# keypad.net
KiCad netlist of a schematic drawn in EAGLE
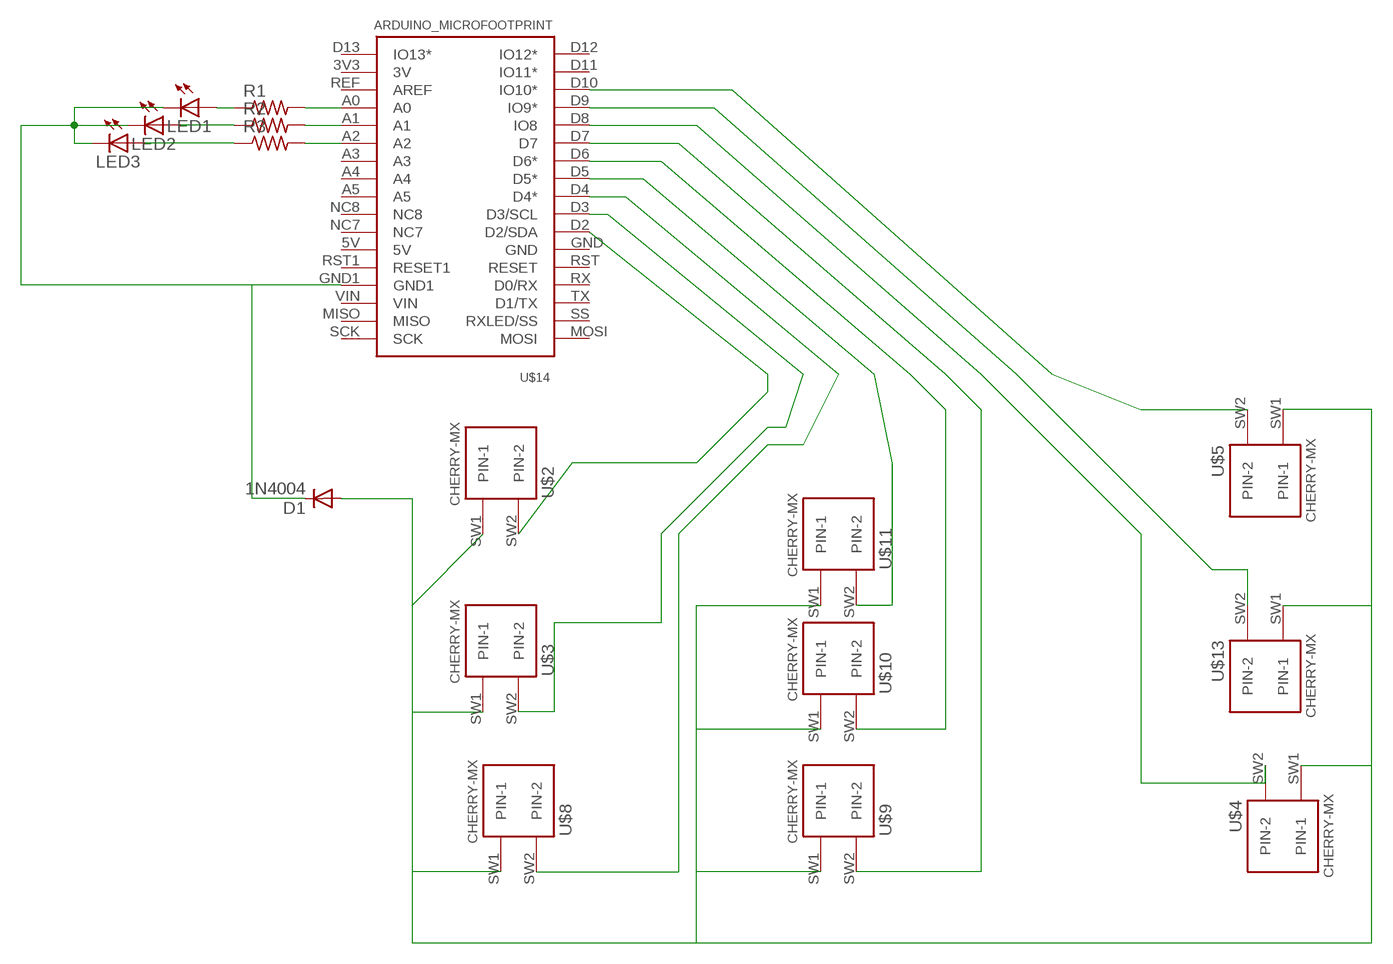
[diagram p0: schematic, sheet 1]

(export (version "E")
  (design (tool "Eeschema 10.0.6"))
  (components
    (comp (ref "D1")
      (value "1N4004")
      (footprint "eagle-import:DO41-10")
      (libsource (lib "eagle-import") (part "1N4004"))
    )
    (comp (ref "LED1")
      (value "LED5MM")
      (footprint "eagle-import:LED5MM")
      (libsource (lib "eagle-import") (part "LED5MM"))
    )
    (comp (ref "LED2")
      (value "LED5MM")
      (footprint "eagle-import:LED5MM")
      (libsource (lib "eagle-import") (part "LED5MM"))
    )
    (comp (ref "LED3")
      (value "LED5MM")
      (footprint "eagle-import:LED5MM")
      (libsource (lib "eagle-import") (part "LED5MM"))
    )
    (comp (ref "R1")
      (value "R-US_0207/5V")
      (footprint "eagle-import:0207_5V")
      (libsource (lib "eagle-import") (part "R-US_0207/5V"))
    )
    (comp (ref "R2")
      (value "R-US_0207/5V")
      (footprint "eagle-import:0207_5V")
      (libsource (lib "eagle-import") (part "R-US_0207/5V"))
    )
    (comp (ref "R3")
      (value "R-US_0207/5V")
      (footprint "eagle-import:0207_5V")
      (libsource (lib "eagle-import") (part "R-US_0207/5V"))
    )
    (comp (ref "U$2")
      (value "CHERRY-MX")
      (footprint "eagle-import:CHERRY-MX")
      (libsource (lib "eagle-import") (part "CHERRY-MX"))
    )
    (comp (ref "U$3")
      (value "CHERRY-MX")
      (footprint "eagle-import:CHERRY-MX")
      (libsource (lib "eagle-import") (part "CHERRY-MX"))
    )
    (comp (ref "U$4")
      (value "CHERRY-MX")
      (footprint "eagle-import:CHERRY-MX")
      (libsource (lib "eagle-import") (part "CHERRY-MX"))
    )
    (comp (ref "U$5")
      (value "CHERRY-MX")
      (footprint "eagle-import:CHERRY-MX")
      (libsource (lib "eagle-import") (part "CHERRY-MX"))
    )
    (comp (ref "U$8")
      (value "CHERRY-MX")
      (footprint "eagle-import:CHERRY-MX")
      (libsource (lib "eagle-import") (part "CHERRY-MX"))
    )
    (comp (ref "U$9")
      (value "CHERRY-MX")
      (footprint "eagle-import:CHERRY-MX")
      (libsource (lib "eagle-import") (part "CHERRY-MX"))
    )
    (comp (ref "U$10")
      (value "CHERRY-MX")
      (footprint "eagle-import:CHERRY-MX")
      (libsource (lib "eagle-import") (part "CHERRY-MX"))
    )
    (comp (ref "U$11")
      (value "CHERRY-MX")
      (footprint "eagle-import:CHERRY-MX")
      (libsource (lib "eagle-import") (part "CHERRY-MX"))
    )
    (comp (ref "U$13")
      (value "CHERRY-MX")
      (footprint "eagle-import:CHERRY-MX")
      (libsource (lib "eagle-import") (part "CHERRY-MX"))
    )
    (comp (ref "U$14")
      (value "ARDUINO_MICROFOOTPRINT")
      (footprint "eagle-import:ARDUINO-MICRO")
      (libsource (lib "eagle-import") (part "ARDUINO_MICROFOOTPRINT"))
    )
  )
  (nets
    (net (code "1") (name "Net-(LED1-C)") (class "Default")
      (node (ref "D1") (pin "C") (pinfunction "C_C") (pintype "passive"))
      (node (ref "LED1") (pin "K") (pinfunction "C_K") (pintype "passive"))
      (node (ref "LED2") (pin "K") (pinfunction "C_K") (pintype "passive"))
      (node (ref "LED3") (pin "K") (pinfunction "C_K") (pintype "passive"))
      (node (ref "U$14") (pin "GND1") (pinfunction "GND1_GND1") (pintype "bidirectional"))
    )
    (net (code "2") (name "Net-(LED1-PadA)") (class "Default")
      (node (ref "LED1") (pin "A") (pinfunction "A_A") (pintype "passive"))
      (node (ref "R1") (pin "1") (pinfunction "1_1") (pintype "passive"))
    )
    (net (code "3") (name "Net-(LED2-PadA)") (class "Default")
      (node (ref "LED2") (pin "A") (pinfunction "A_A") (pintype "passive"))
      (node (ref "R2") (pin "1") (pinfunction "1_1") (pintype "passive"))
    )
    (net (code "4") (name "Net-(LED3-PadA)") (class "Default")
      (node (ref "LED3") (pin "A") (pinfunction "A_A") (pintype "passive"))
      (node (ref "R3") (pin "1") (pinfunction "1_1") (pintype "passive"))
    )
    (net (code "5") (name "Net-(R1-Pad2)") (class "Default")
      (node (ref "R1") (pin "2") (pinfunction "2_2") (pintype "passive"))
      (node (ref "U$14") (pin "A0") (pinfunction "A0_A0") (pintype "bidirectional"))
    )
    (net (code "6") (name "Net-(R2-Pad2)") (class "Default")
      (node (ref "R2") (pin "2") (pinfunction "2_2") (pintype "passive"))
      (node (ref "U$14") (pin "A1") (pinfunction "A1_A1") (pintype "bidirectional"))
    )
    (net (code "7") (name "Net-(R3-Pad2)") (class "Default")
      (node (ref "R3") (pin "2") (pinfunction "2_2") (pintype "passive"))
      (node (ref "U$14") (pin "A2") (pinfunction "A2_A2") (pintype "bidirectional"))
    )
    (net (code "8") (name "Net-(U$9-PIN-2)") (class "Default")
      (node (ref "U$14") (pin "D7") (pinfunction "D7_D7") (pintype "bidirectional"))
      (node (ref "U$9") (pin "SW2") (pinfunction "PIN-2_SW2") (pintype "bidirectional"))
    )
    (net (code "9") (name "Net-(U$10-PIN-1)") (class "Default")
      (node (ref "D1") (pin "A") (pinfunction "A_A") (pintype "passive"))
      (node (ref "U$10") (pin "SW1") (pinfunction "PIN-1_SW1") (pintype "bidirectional"))
      (node (ref "U$11") (pin "SW1") (pinfunction "PIN-1_SW1") (pintype "bidirectional"))
      (node (ref "U$13") (pin "SW1") (pinfunction "PIN-1_SW1") (pintype "bidirectional"))
      (node (ref "U$2") (pin "SW1") (pinfunction "PIN-1_SW1") (pintype "bidirectional"))
      (node (ref "U$3") (pin "SW1") (pinfunction "PIN-1_SW1") (pintype "bidirectional"))
      (node (ref "U$4") (pin "SW1") (pinfunction "PIN-1_SW1") (pintype "bidirectional"))
      (node (ref "U$5") (pin "SW1") (pinfunction "PIN-1_SW1") (pintype "bidirectional"))
      (node (ref "U$8") (pin "SW1") (pinfunction "PIN-1_SW1") (pintype "bidirectional"))
      (node (ref "U$9") (pin "SW1") (pinfunction "PIN-1_SW1") (pintype "bidirectional"))
    )
    (net (code "10") (name "Net-(U$10-PIN-2)") (class "Default")
      (node (ref "U$10") (pin "SW2") (pinfunction "PIN-2_SW2") (pintype "bidirectional"))
      (node (ref "U$14") (pin "D6") (pinfunction "D6*_D6") (pintype "bidirectional"))
    )
    (net (code "11") (name "Net-(U$11-PIN-2)") (class "Default")
      (node (ref "U$11") (pin "SW2") (pinfunction "PIN-2_SW2") (pintype "bidirectional"))
      (node (ref "U$14") (pin "D5") (pinfunction "D5*_D5") (pintype "bidirectional"))
    )
    (net (code "12") (name "Net-(U$13-PIN-2)") (class "Default")
      (node (ref "U$13") (pin "SW2") (pinfunction "PIN-2_SW2") (pintype "bidirectional"))
      (node (ref "U$14") (pin "D9") (pinfunction "IO9*_D9") (pintype "bidirectional"))
    )
    (net (code "13") (name "Net-(U$14-D2{slash}SDA)") (class "Default")
      (node (ref "U$14") (pin "D2") (pinfunction "D2/SDA_D2") (pintype "bidirectional"))
      (node (ref "U$2") (pin "SW2") (pinfunction "PIN-2_SW2") (pintype "bidirectional"))
    )
    (net (code "14") (name "Net-(U$14-D3{slash}SCL)") (class "Default")
      (node (ref "U$14") (pin "D3") (pinfunction "D3/SCL_D3") (pintype "bidirectional"))
      (node (ref "U$3") (pin "SW2") (pinfunction "PIN-2_SW2") (pintype "bidirectional"))
    )
    (net (code "15") (name "Net-(U$14-D4*)") (class "Default")
      (node (ref "U$14") (pin "D4") (pinfunction "D4*_D4") (pintype "bidirectional"))
      (node (ref "U$8") (pin "SW2") (pinfunction "PIN-2_SW2") (pintype "bidirectional"))
    )
    (net (code "16") (name "Net-(U$14-IO8)") (class "Default")
      (node (ref "U$14") (pin "D8") (pinfunction "IO8_D8") (pintype "bidirectional"))
      (node (ref "U$4") (pin "SW2") (pinfunction "PIN-2_SW2") (pintype "bidirectional"))
    )
    (net (code "17") (name "Net-(U$14-IO10*)") (class "Default")
      (node (ref "U$14") (pin "D10") (pinfunction "IO10*_D10") (pintype "bidirectional"))
      (node (ref "U$5") (pin "SW2") (pinfunction "PIN-2_SW2") (pintype "bidirectional"))
    )
    (net (code "18") (name "unconnected-(U$14-3V-Pad3V3)") (class "Default")
      (node (ref "U$14") (pin "3V3") (pinfunction "3V_3V3") (pintype "bidirectional"))
    )
    (net (code "19") (name "unconnected-(U$14-AREF-PadREF)") (class "Default")
      (node (ref "U$14") (pin "REF") (pinfunction "AREF_REF") (pintype "bidirectional"))
    )
    (net (code "20") (name "unconnected-(U$14-D0{slash}RX-PadRX)") (class "Default")
      (node (ref "U$14") (pin "RX") (pinfunction "D0/RX_RX") (pintype "bidirectional"))
    )
    (net (code "21") (name "unconnected-(U$14-D1{slash}TX-PadTX)") (class "Default")
      (node (ref "U$14") (pin "TX") (pinfunction "D1/TX_TX") (pintype "bidirectional"))
    )
    (net (code "22") (name "unconnected-(U$14-IO11*-PadD11)") (class "Default")
      (node (ref "U$14") (pin "D11") (pinfunction "IO11*_D11") (pintype "bidirectional"))
    )
    (net (code "23") (name "unconnected-(U$14-IO12*-PadD12)") (class "Default")
      (node (ref "U$14") (pin "D12") (pinfunction "IO12*_D12") (pintype "bidirectional"))
    )
    (net (code "24") (name "unconnected-(U$14-IO13*-PadD13)") (class "Default")
      (node (ref "U$14") (pin "D13") (pinfunction "IO13*_D13") (pintype "bidirectional"))
    )
    (net (code "25") (name "unconnected-(U$14-Pad5V)") (class "Default")
      (node (ref "U$14") (pin "5V") (pinfunction "5V_5V") (pintype "bidirectional"))
    )
    (net (code "26") (name "unconnected-(U$14-PadA3)") (class "Default")
      (node (ref "U$14") (pin "A3") (pinfunction "A3_A3") (pintype "bidirectional"))
    )
    (net (code "27") (name "unconnected-(U$14-PadA4)") (class "Default")
      (node (ref "U$14") (pin "A4") (pinfunction "A4_A4") (pintype "bidirectional"))
    )
    (net (code "28") (name "unconnected-(U$14-PadA5)") (class "Default")
      (node (ref "U$14") (pin "A5") (pinfunction "A5_A5") (pintype "bidirectional"))
    )
    (net (code "29") (name "unconnected-(U$14-PadGND)") (class "Default")
      (node (ref "U$14") (pin "GND") (pinfunction "GND_GND") (pintype "bidirectional"))
    )
    (net (code "30") (name "unconnected-(U$14-PadMISO)") (class "Default")
      (node (ref "U$14") (pin "MISO") (pinfunction "MISO_MISO") (pintype "bidirectional"))
    )
    (net (code "31") (name "unconnected-(U$14-PadMOSI)") (class "Default")
      (node (ref "U$14") (pin "MOSI") (pinfunction "MOSI_MOSI") (pintype "bidirectional"))
    )
    (net (code "32") (name "unconnected-(U$14-PadNC7)") (class "Default")
      (node (ref "U$14") (pin "NC7") (pinfunction "NC7_NC7") (pintype "bidirectional"))
    )
    (net (code "33") (name "unconnected-(U$14-PadNC8)") (class "Default")
      (node (ref "U$14") (pin "NC8") (pinfunction "NC8_NC8") (pintype "bidirectional"))
    )
    (net (code "34") (name "unconnected-(U$14-PadSCK)") (class "Default")
      (node (ref "U$14") (pin "SCK") (pinfunction "SCK_SCK") (pintype "bidirectional"))
    )
    (net (code "35") (name "unconnected-(U$14-PadVIN)") (class "Default")
      (node (ref "U$14") (pin "VIN") (pinfunction "VIN_VIN") (pintype "bidirectional"))
    )
    (net (code "36") (name "unconnected-(U$14-RESET-PadRST)") (class "Default")
      (node (ref "U$14") (pin "RST") (pinfunction "RESET_RST") (pintype "bidirectional"))
    )
    (net (code "37") (name "unconnected-(U$14-RESET1-PadRST1)") (class "Default")
      (node (ref "U$14") (pin "RST1") (pinfunction "RESET1_RST1") (pintype "bidirectional"))
    )
    (net (code "38") (name "unconnected-(U$14-RXLED{slash}SS-PadSS)") (class "Default")
      (node (ref "U$14") (pin "SS") (pinfunction "RXLED/SS_SS") (pintype "bidirectional"))
    )
  )
)
